# SCH_uCompute_NRF24L01_module_2026-03-14.net
KiCad netlist of a schematic drawn in EasyEDA
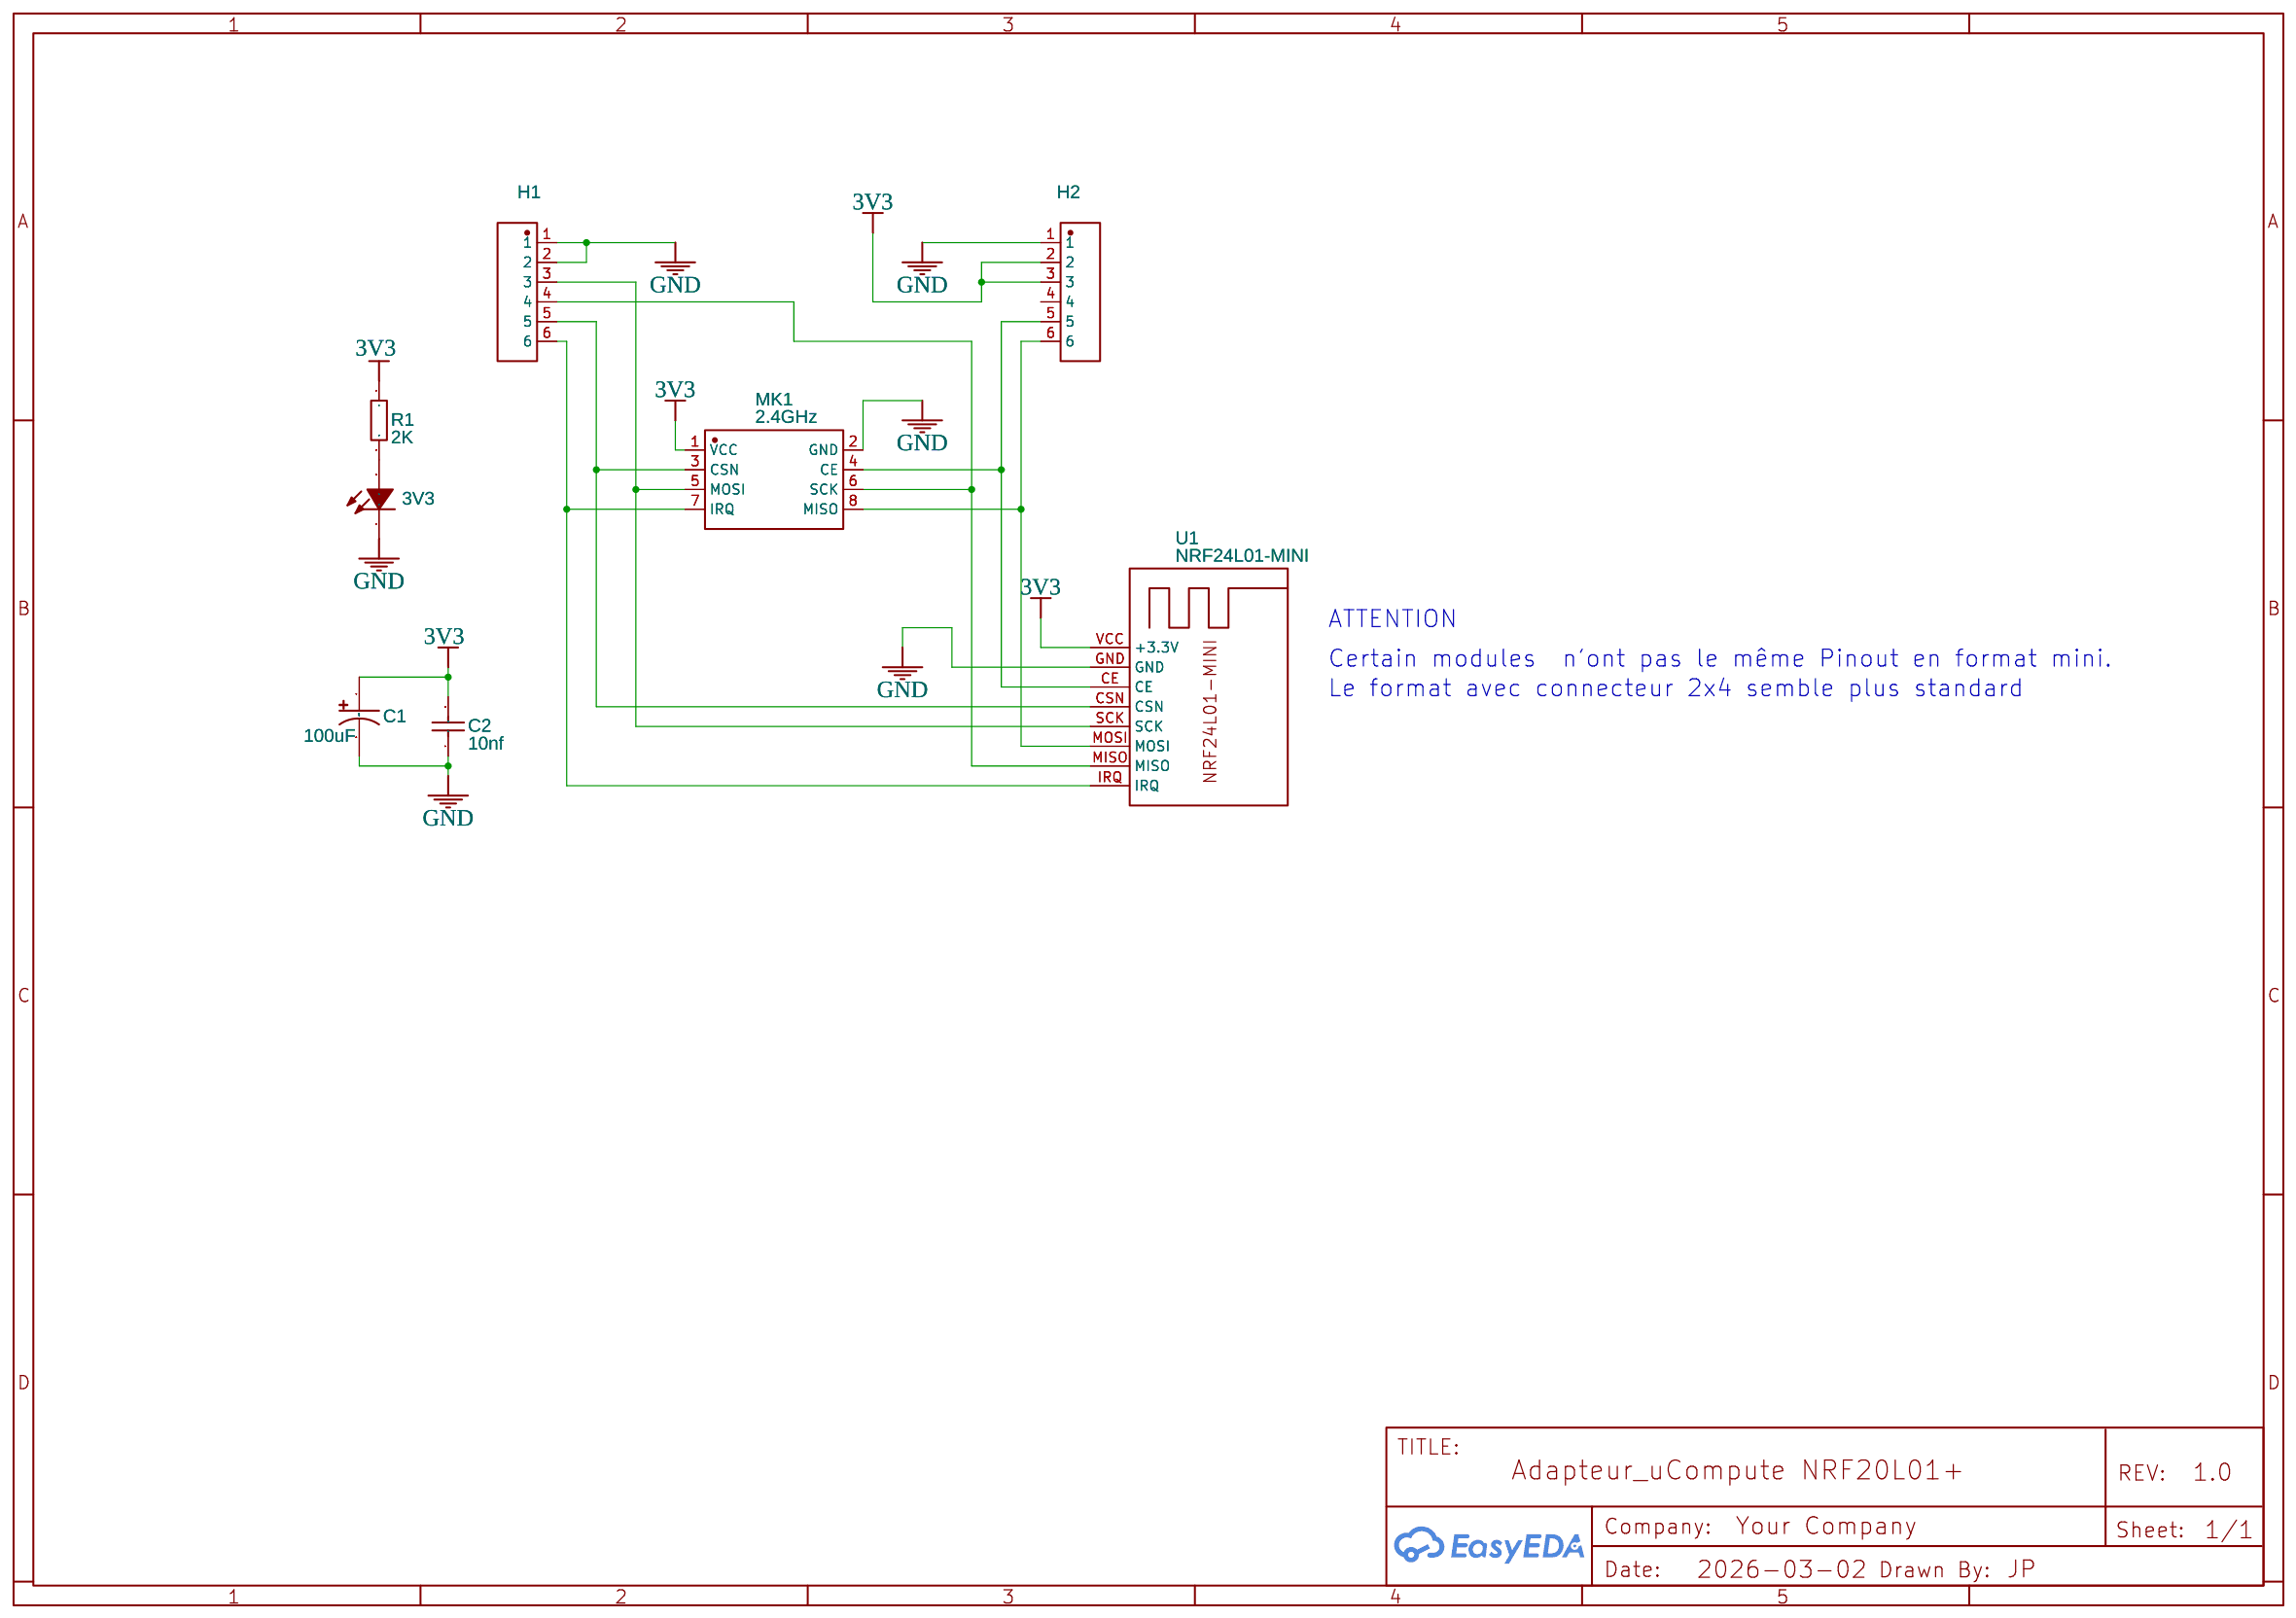
[diagram p0: schematic sheet]

(export (version "E")
  (design (tool "Eeschema 10.0.6"))
  (components
    (comp (ref "3V3")
      (value "XL-1206QPC")
      (fields (field (name "Manufacturer") "LCSC"))
      (libsource (lib "") (part "XL-1206QPC"))
    )
    (comp (ref "C1")
      (value "100uF")
      (fields
        (field (name "Manufacturer Part") "TLJA107M010R1400")
        (field (name "Manufacturer") "Kyocera AVX")
      )
      (libsource (lib "") (part "TLJA107M010R1400"))
    )
    (comp (ref "C2")
      (value "10nf")
      (fields (field (name "Manufacturer Part") "0805CG220J500NT") (field (name "Manufacturer") "FH"))
      (libsource (lib "") (part "0805CG220J500NT"))
    )
    (comp (ref "H1")
      (value "KH-2.54PH180-1X6P-L11.5")
      (fields (field (name "Manufacturer") "kinghelm(金航标)"))
      (libsource (lib "") (part "KH-2.54PH180-1X6P-L11.5_1"))
    )
    (comp (ref "H2")
      (value "KH-2.54PH180-1X6P-L11.5")
      (fields (field (name "Manufacturer") "kinghelm(金航标)"))
      (libsource (lib "") (part "KH-2.54PH180-1X6P-L11.5"))
    )
    (comp (ref "MK1")
      (value "2.4GHz")
      (fields (field (name "Manufacturer Part") "NF-04") (field (name "Manufacturer") "Ai-Thinker(安信可)"))
      (libsource (lib "") (part "NRF24L01"))
    )
    (comp (ref "R1")
      (value "2K")
      (fields (field (name "Manufacturer Part") "RC0805DR-071KL") (field (name "Manufacturer") "YAGEO(国巨)"))
      (libsource (lib "") (part "RC0805DR-071KL"))
    )
    (comp (ref "U1") (value "NRF24L01-MINI") (libsource (lib "") (part "NRF24L01-MINI")))
  )
  (nets
    (net (code "1") (name "3V3") (class "Default")
      (node (ref "C1") (pin "1") (pinfunction "1_1") (pintype "unspecified"))
      (node (ref "C2") (pin "2") (pinfunction "2_2") (pintype "input"))
      (node (ref "H2") (pin "2") (pinfunction "2_2") (pintype "unspecified"))
      (node (ref "H2") (pin "3") (pinfunction "3_3") (pintype "unspecified"))
      (node (ref "MK1") (pin "1") (pinfunction "VCC_1") (pintype "unspecified"))
      (node (ref "R1") (pin "1") (pinfunction "1_1") (pintype "unspecified"))
      (node (ref "U1") (pin "VCC") (pinfunction "+3.3V_VCC") (pintype "passive"))
    )
    (net (code "2") (name "GND") (class "Default")
      (node (ref "3V3") (pin "1") (pinfunction "K_1") (pintype "unspecified"))
      (node (ref "C1") (pin "2") (pinfunction "2_2") (pintype "unspecified"))
      (node (ref "C2") (pin "1") (pinfunction "1_1") (pintype "input"))
      (node (ref "H1") (pin "1") (pinfunction "1_1") (pintype "unspecified"))
      (node (ref "H1") (pin "2") (pinfunction "2_2") (pintype "unspecified"))
      (node (ref "H2") (pin "1") (pinfunction "1_1") (pintype "unspecified"))
      (node (ref "MK1") (pin "2") (pinfunction "GND_2") (pintype "unspecified"))
      (node (ref "U1") (pin "GND") (pinfunction "GND_GND") (pintype "unspecified"))
    )
    (net (code "3") (name "Net-(3V3-A)") (class "Default")
      (node (ref "3V3") (pin "2") (pinfunction "A_2") (pintype "unspecified"))
      (node (ref "R1") (pin "2") (pinfunction "2_2") (pintype "unspecified"))
    )
    (net (code "4") (name "Net-(MK1-CE)") (class "Default")
      (node (ref "H2") (pin "5") (pinfunction "5_5") (pintype "unspecified"))
      (node (ref "MK1") (pin "4") (pinfunction "CE_4") (pintype "unspecified"))
      (node (ref "U1") (pin "CE") (pinfunction "CE_CE") (pintype "bidirectional"))
    )
    (net (code "5") (name "Net-(MK1-CSN)") (class "Default")
      (node (ref "H1") (pin "5") (pinfunction "5_5") (pintype "unspecified"))
      (node (ref "MK1") (pin "3") (pinfunction "CSN_3") (pintype "unspecified"))
      (node (ref "U1") (pin "CSN") (pinfunction "CSN_CSN") (pintype "bidirectional"))
    )
    (net (code "6") (name "Net-(MK1-IRQ)") (class "Default")
      (node (ref "H1") (pin "6") (pinfunction "6_6") (pintype "unspecified"))
      (node (ref "MK1") (pin "7") (pinfunction "IRQ_7") (pintype "unspecified"))
      (node (ref "U1") (pin "IRQ") (pinfunction "IRQ_IRQ") (pintype "unspecified"))
    )
    (net (code "7") (name "Net-(MK1-MISO)") (class "Default")
      (node (ref "H2") (pin "6") (pinfunction "6_6") (pintype "unspecified"))
      (node (ref "MK1") (pin "8") (pinfunction "MISO_8") (pintype "unspecified"))
      (node (ref "U1") (pin "MOSI") (pinfunction "MOSI_MOSI") (pintype "bidirectional"))
    )
    (net (code "8") (name "Net-(MK1-MOSI)") (class "Default")
      (node (ref "H1") (pin "3") (pinfunction "3_3") (pintype "unspecified"))
      (node (ref "MK1") (pin "5") (pinfunction "MOSI_5") (pintype "unspecified"))
      (node (ref "U1") (pin "SCK") (pinfunction "SCK_SCK") (pintype "bidirectional"))
    )
    (net (code "9") (name "Net-(MK1-SCK)") (class "Default")
      (node (ref "H1") (pin "4") (pinfunction "4_4") (pintype "unspecified"))
      (node (ref "MK1") (pin "6") (pinfunction "SCK_6") (pintype "unspecified"))
      (node (ref "U1") (pin "MISO") (pinfunction "MISO_MISO") (pintype "output"))
    )
    (net (code "10") (name "unconnected-(H2-Pad4)") (class "Default")
      (node (ref "H2") (pin "4") (pinfunction "4_4") (pintype "unspecified"))
    )
  )
)
